# Multi_HUTSCHIENE_EXT_1_1.net
KiCad netlist of a schematic drawn in Altium Designer
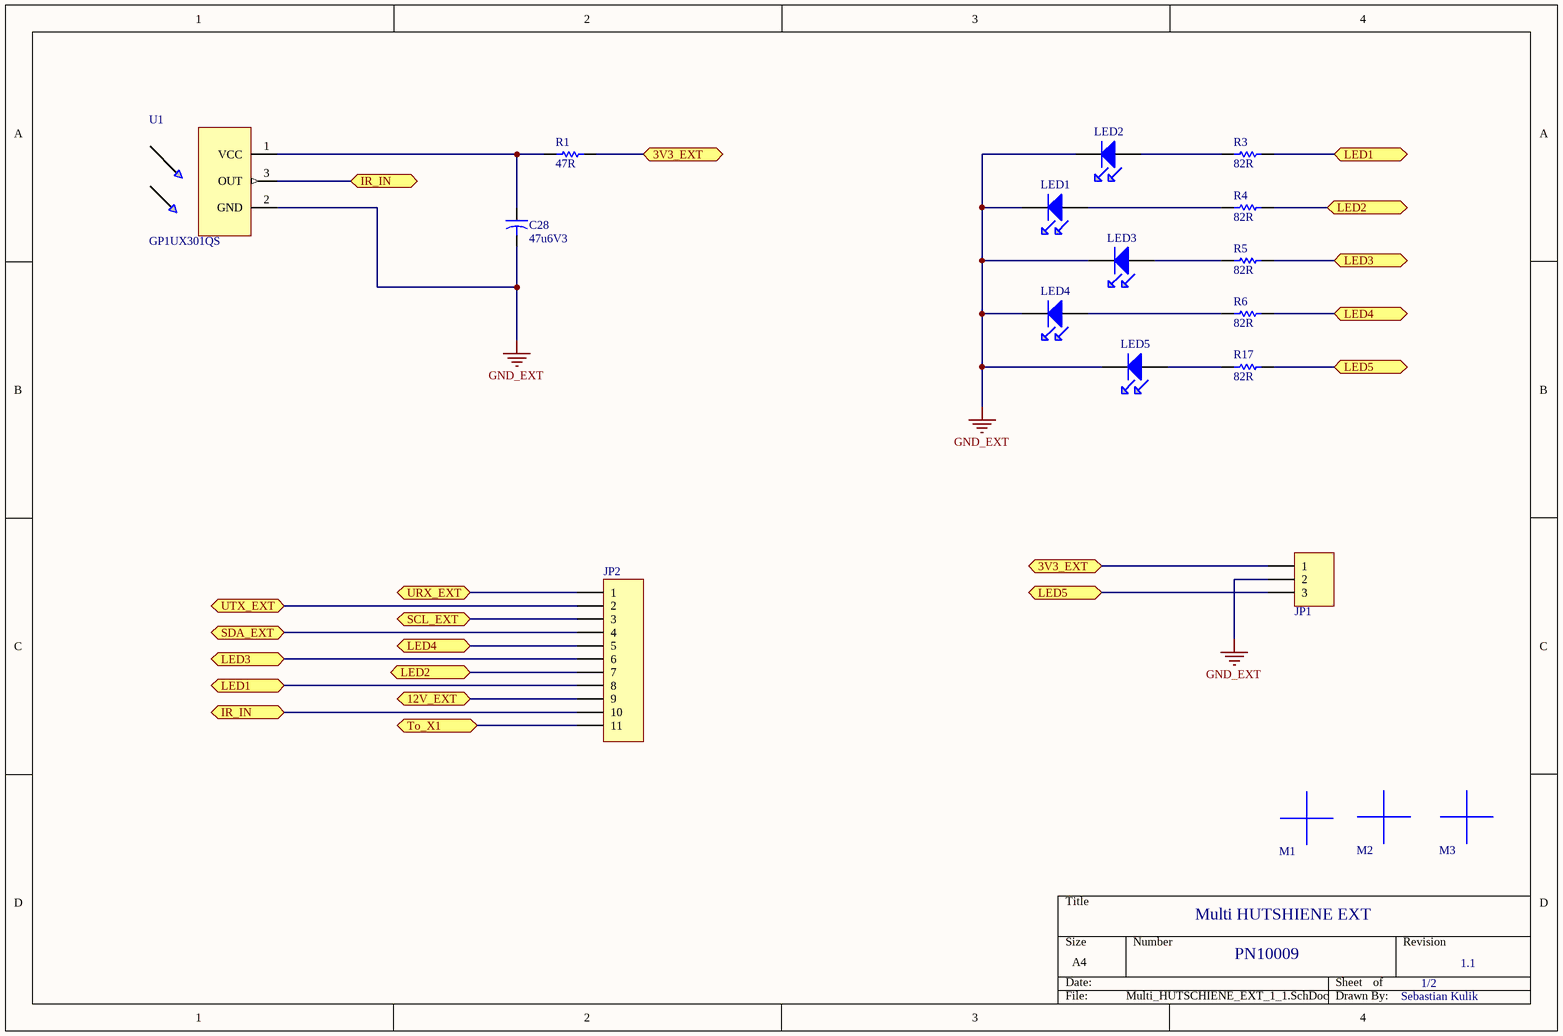
[diagram p0: Multi_HUTSCHIENE_EXT_1_1.SchDoc]

(export (version "E")
  (design (tool "Eeschema 10.0.6"))
  (components
    (comp (ref "C28")
      (value "47u6V3")
      (footprint "C0805")
      (description "Kemet  C series, X5R, 20%, 6.3V")
      (fields
        (field (name "MANUFACTURER") "Kemet")
        (field (name "Comment") "47u6V3_0805")
        (field (name "PUBLISHER") "Sebastian Kulik")
      )
      (libsource (lib "Capacitors") (part "47u6V3_0805"))
    )
    (comp (ref "JP1")
      (value "Plug_3_90_2.54")
      (footprint "HDR1X3-DOWN")
      (description "Plug,-3-Pin")
      (fields (field (name "MANUFACTURER") "WE") (field (name "PUBLISHER") "Sebastian Kulik"))
      (libsource (lib "Connectors") (part "Plug_3_90_2.54"))
    )
    (comp (ref "JP2")
      (value "Plug_11_90_2.54")
      (footprint "HDR1X11_2.54-DOWN")
      (description "Plug, 11-Pin")
      (fields (field (name "MANUFACTURER") "Semtec") (field (name "PUBLISHER") "Sebastian Kulik"))
      (libsource (lib "Connectors") (part "Plug_11_90_2.54"))
    )
    (comp (ref "LED1")
      (value "HSMG-120-Y")
      (footprint "HSMA-120-OR")
      (description "LED, 90°, yellow")
      (fields (field (name "MANUFACTURER") "Avago") (field (name "PUBLISHER") "Sebastian Kulik"))
      (libsource (lib "Discrete") (part "HSMG-120-Y"))
    )
    (comp (ref "LED2")
      (value "HSMG-120-GR")
      (footprint "HSMA-120-G")
      (description "LED, 90°, green")
      (fields (field (name "MANUFACTURER") "Avago") (field (name "PUBLISHER") "Sebastian Kulik"))
      (libsource (lib "Discrete") (part "HSMG-120-GR"))
    )
    (comp (ref "LED3")
      (value "HSMG-120-Y")
      (footprint "HSMA-120-OR")
      (description "LED, 90°, yellow")
      (fields (field (name "MANUFACTURER") "Avago") (field (name "PUBLISHER") "Sebastian Kulik"))
      (libsource (lib "Discrete") (part "HSMG-120-Y"))
    )
    (comp (ref "LED4")
      (value "HSMG-120-Y")
      (footprint "HSMA-120-OR")
      (description "LED, 90°, yellow")
      (fields (field (name "MANUFACTURER") "Avago") (field (name "PUBLISHER") "Sebastian Kulik"))
      (libsource (lib "Discrete") (part "HSMG-120-Y"))
    )
    (comp (ref "LED5")
      (value "HSMG-120-Y")
      (footprint "HSMA-120-OR")
      (description "LED, 90°, yellow")
      (fields (field (name "MANUFACTURER") "Avago") (field (name "PUBLISHER") "Sebastian Kulik"))
      (libsource (lib "Discrete") (part "HSMG-120-Y"))
    )
    (comp (ref "M1") (value "Mark") (footprint "Mark-3mm") (libsource (lib "Symbols") (part "Mark")))
    (comp (ref "M2") (value "Mark") (footprint "Mark-3mm") (libsource (lib "Symbols") (part "Mark")))
    (comp (ref "M3") (value "Mark") (footprint "Mark-3mm") (libsource (lib "Symbols") (part "Mark")))
    (comp (ref "R1")
      (value "47R")
      (footprint "R0603(1608)")
      (description "Vishay, CRCW series, 100mW, 1%")
      (fields
        (field (name "MANUFACTURER") "Vishay")
        (field (name "Comment") "47R_0603")
        (field (name "PUBLISHER") "Sebastian Kulik")
      )
      (libsource (lib "Resistors") (part "47R_0603"))
    )
    (comp (ref "R3")
      (value "82R")
      (footprint "R0603(1608)")
      (description "Vishay, CRCW series, 100mW, 1%")
      (fields
        (field (name "MANUFACTURER") "Vishay")
        (field (name "Comment") "82R_0603")
        (field (name "PUBLISHER") "Sebastian Kulik")
      )
      (libsource (lib "Resistors") (part "82R_0603"))
    )
    (comp (ref "R4")
      (value "82R")
      (footprint "R0603(1608)")
      (description "Vishay, CRCW series, 100mW, 1%")
      (fields
        (field (name "MANUFACTURER") "Vishay")
        (field (name "Comment") "82R_0603")
        (field (name "PUBLISHER") "Sebastian Kulik")
      )
      (libsource (lib "Resistors") (part "82R_0603"))
    )
    (comp (ref "R5")
      (value "82R")
      (footprint "R0603(1608)")
      (description "Vishay, CRCW series, 100mW, 1%")
      (fields
        (field (name "MANUFACTURER") "Vishay")
        (field (name "Comment") "82R_0603")
        (field (name "PUBLISHER") "Sebastian Kulik")
      )
      (libsource (lib "Resistors") (part "82R_0603"))
    )
    (comp (ref "R6")
      (value "82R")
      (footprint "R0603(1608)")
      (description "Vishay, CRCW series, 100mW, 1%")
      (fields
        (field (name "MANUFACTURER") "Vishay")
        (field (name "Comment") "82R_0603")
        (field (name "PUBLISHER") "Sebastian Kulik")
      )
      (libsource (lib "Resistors") (part "82R_0603"))
    )
    (comp (ref "R17")
      (value "82R")
      (footprint "R0603(1608)")
      (description "Vishay, CRCW series, 100mW, 1%")
      (fields
        (field (name "MANUFACTURER") "Vishay")
        (field (name "Comment") "82R_0603")
        (field (name "PUBLISHER") "Sebastian Kulik")
      )
      (libsource (lib "Resistors") (part "82R_0603"))
    )
    (comp (ref "U1")
      (value "GP1UX301QS")
      (footprint "IR-GP")
      (description "IR reseiver")
      (fields (field (name "MANUFACTURER") "Sharp") (field (name "PUBLISHER") "Sebastian Kulik"))
      (libsource (lib "ICs") (part "GP1UX301QS"))
    )
  )
  (nets
    (net (code "1") (name "/3V3_EXT") (class "Default")
      (node (ref "JP1") (pin "1") (pinfunction "1_1") (pintype "passive"))
      (node (ref "R1") (pin "2") (pinfunction "2_2") (pintype "passive"))
    )
    (net (code "2") (name "/12V_EXT") (class "Default")
      (node (ref "JP2") (pin "9") (pinfunction "9_9") (pintype "passive"))
    )
    (net (code "3") (name "/IR_IN") (class "Default")
      (node (ref "JP2") (pin "10") (pinfunction "10_10") (pintype "passive"))
      (node (ref "U1") (pin "3") (pinfunction "OUT_3") (pintype "output"))
    )
    (net (code "4") (name "/LED1") (class "Default")
      (node (ref "JP2") (pin "8") (pinfunction "8_8") (pintype "passive"))
      (node (ref "R3") (pin "2") (pinfunction "2_2") (pintype "passive"))
    )
    (net (code "5") (name "/LED2") (class "Default")
      (node (ref "JP2") (pin "7") (pinfunction "7_7") (pintype "passive"))
      (node (ref "R4") (pin "2") (pinfunction "2_2") (pintype "passive"))
    )
    (net (code "6") (name "/LED3") (class "Default")
      (node (ref "JP2") (pin "6") (pinfunction "6_6") (pintype "passive"))
      (node (ref "R5") (pin "2") (pinfunction "2_2") (pintype "passive"))
    )
    (net (code "7") (name "/LED4") (class "Default")
      (node (ref "JP2") (pin "5") (pinfunction "5_5") (pintype "passive"))
      (node (ref "R6") (pin "2") (pinfunction "2_2") (pintype "passive"))
    )
    (net (code "8") (name "/LED5") (class "Default")
      (node (ref "JP1") (pin "3") (pinfunction "3_3") (pintype "passive"))
      (node (ref "R17") (pin "2") (pinfunction "2_2") (pintype "passive"))
    )
    (net (code "9") (name "/SCL_EXT") (class "Default")
      (node (ref "JP2") (pin "3") (pinfunction "3_3") (pintype "passive"))
    )
    (net (code "10") (name "/SDA_EXT") (class "Default")
      (node (ref "JP2") (pin "4") (pinfunction "4_4") (pintype "passive"))
    )
    (net (code "11") (name "/To_X1") (class "Default")
      (node (ref "JP2") (pin "11") (pinfunction "11_11") (pintype "passive"))
    )
    (net (code "12") (name "/URX_EXT") (class "Default")
      (node (ref "JP2") (pin "1") (pinfunction "1_1") (pintype "passive"))
    )
    (net (code "13") (name "/UTX_EXT") (class "Default")
      (node (ref "JP2") (pin "2") (pinfunction "2_2") (pintype "passive"))
    )
    (net (code "14") (name "GND_EXT") (class "Default")
      (node (ref "C28") (pin "2") (pinfunction "2_2") (pintype "passive"))
      (node (ref "JP1") (pin "2") (pinfunction "2_2") (pintype "passive"))
      (node (ref "LED1") (pin "1") (pinfunction "K_1") (pintype "passive"))
      (node (ref "LED2") (pin "1") (pinfunction "K_1") (pintype "passive"))
      (node (ref "LED3") (pin "1") (pinfunction "K_1") (pintype "passive"))
      (node (ref "LED4") (pin "1") (pinfunction "K_1") (pintype "passive"))
      (node (ref "LED5") (pin "1") (pinfunction "K_1") (pintype "passive"))
      (node (ref "U1") (pin "2") (pinfunction "GND_2") (pintype "power_in"))
    )
    (net (code "15") (name "Net-(LED1-A)") (class "Default")
      (node (ref "LED1") (pin "2") (pinfunction "A_2") (pintype "passive"))
      (node (ref "R4") (pin "1") (pinfunction "1_1") (pintype "passive"))
    )
    (net (code "16") (name "Net-(LED2-A)") (class "Default")
      (node (ref "LED2") (pin "2") (pinfunction "A_2") (pintype "passive"))
      (node (ref "R3") (pin "1") (pinfunction "1_1") (pintype "passive"))
    )
    (net (code "17") (name "Net-(LED3-A)") (class "Default")
      (node (ref "LED3") (pin "2") (pinfunction "A_2") (pintype "passive"))
      (node (ref "R5") (pin "1") (pinfunction "1_1") (pintype "passive"))
    )
    (net (code "18") (name "Net-(LED4-A)") (class "Default")
      (node (ref "LED4") (pin "2") (pinfunction "A_2") (pintype "passive"))
      (node (ref "R6") (pin "1") (pinfunction "1_1") (pintype "passive"))
    )
    (net (code "19") (name "Net-(LED5-A)") (class "Default")
      (node (ref "LED5") (pin "2") (pinfunction "A_2") (pintype "passive"))
      (node (ref "R17") (pin "1") (pinfunction "1_1") (pintype "passive"))
    )
    (net (code "20") (name "Net-(U1-VCC)") (class "Default")
      (node (ref "C28") (pin "1") (pinfunction "1_1") (pintype "passive"))
      (node (ref "R1") (pin "1") (pinfunction "1_1") (pintype "passive"))
      (node (ref "U1") (pin "1") (pinfunction "VCC_1") (pintype "power_in"))
    )
  )
)
